# WeightGauge.net
KiCad netlist of a schematic drawn in EAGLE
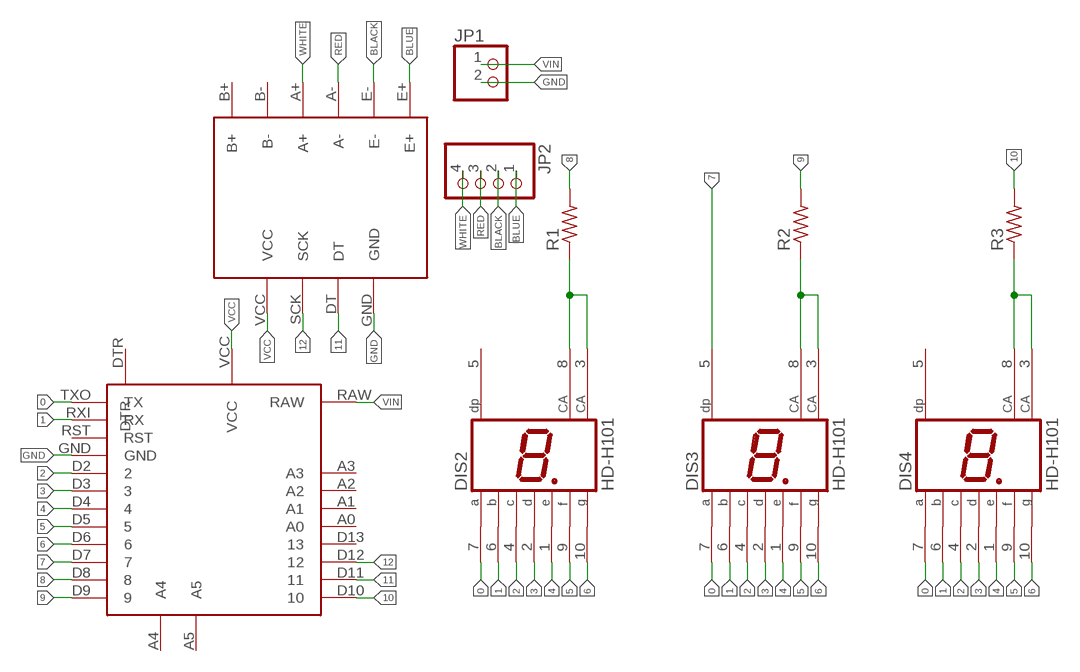
[diagram p0: schematic, sheet 1]

(export (version "E")
  (design (tool "Eeschema 10.0.6"))
  (components
    (comp (ref "DIS2")
      (value "HD-H101")
      (footprint "eagle-import:HDSP-M")
      (libsource (lib "eagle-import") (part "HD-H101"))
    )
    (comp (ref "DIS3")
      (value "HD-H101")
      (footprint "eagle-import:HDSP-M")
      (libsource (lib "eagle-import") (part "HD-H101"))
    )
    (comp (ref "DIS4")
      (value "HD-H101")
      (footprint "eagle-import:HDSP-M")
      (libsource (lib "eagle-import") (part "HD-H101"))
    )
    (comp (ref "JP1")
      (value "PINHD-1X2/90")
      (footprint "eagle-import:1X02_90")
      (libsource (lib "eagle-import") (part "PINHD-1X2/90"))
    )
    (comp (ref "JP2")
      (value "PINHD-1X4/90")
      (footprint "eagle-import:1X04_90")
      (libsource (lib "eagle-import") (part "PINHD-1X4/90"))
    )
    (comp (ref "R1")
      (value "R-US_R1206")
      (footprint "eagle-import:R1206")
      (libsource (lib "eagle-import") (part "R-US_R1206"))
    )
    (comp (ref "R2")
      (value "R-US_R1206")
      (footprint "eagle-import:R1206")
      (libsource (lib "eagle-import") (part "R-US_R1206"))
    )
    (comp (ref "R3")
      (value "R-US_R1206")
      (footprint "eagle-import:R1206")
      (libsource (lib "eagle-import") (part "R-US_R1206"))
    )
    (comp (ref "U$1")
      (value "ARDUINO_PRO_MINI")
      (footprint "eagle-import:ARDUINO_PRO_MINI")
      (libsource (lib "eagle-import") (part "ARDUINO_PRO_MINI"))
    )
    (comp (ref "U$2")
      (value "HX711")
      (footprint "eagle-import:HX711")
      (libsource (lib "eagle-import") (part "HX711"))
    )
  )
  (nets
    (net (code "1") (name "0") (class "Default")
      (node (ref "DIS2") (pin "7") (pinfunction "A_7") (pintype "passive"))
      (node (ref "DIS3") (pin "7") (pinfunction "A_7") (pintype "passive"))
      (node (ref "DIS4") (pin "7") (pinfunction "A_7") (pintype "passive"))
      (node (ref "U$1") (pin "TXO") (pinfunction "TX_TXO") (pintype "bidirectional"))
    )
    (net (code "2") (name "1") (class "Default")
      (node (ref "DIS2") (pin "6") (pinfunction "B_6") (pintype "passive"))
      (node (ref "DIS3") (pin "6") (pinfunction "B_6") (pintype "passive"))
      (node (ref "DIS4") (pin "6") (pinfunction "B_6") (pintype "passive"))
      (node (ref "U$1") (pin "RXI") (pinfunction "RX_RXI") (pintype "bidirectional"))
    )
    (net (code "3") (name "2") (class "Default")
      (node (ref "DIS2") (pin "4") (pinfunction "C_4") (pintype "passive"))
      (node (ref "DIS3") (pin "4") (pinfunction "C_4") (pintype "passive"))
      (node (ref "DIS4") (pin "4") (pinfunction "C_4") (pintype "passive"))
      (node (ref "U$1") (pin "D2") (pinfunction "2_D2") (pintype "bidirectional"))
    )
    (net (code "4") (name "3") (class "Default")
      (node (ref "DIS2") (pin "2") (pinfunction "D_2") (pintype "passive"))
      (node (ref "DIS3") (pin "2") (pinfunction "D_2") (pintype "passive"))
      (node (ref "DIS4") (pin "2") (pinfunction "D_2") (pintype "passive"))
      (node (ref "U$1") (pin "D3") (pinfunction "3_D3") (pintype "bidirectional"))
    )
    (net (code "5") (name "4") (class "Default")
      (node (ref "DIS2") (pin "1") (pinfunction "E_1") (pintype "passive"))
      (node (ref "DIS3") (pin "1") (pinfunction "E_1") (pintype "passive"))
      (node (ref "DIS4") (pin "1") (pinfunction "E_1") (pintype "passive"))
      (node (ref "U$1") (pin "D4") (pinfunction "4_D4") (pintype "bidirectional"))
    )
    (net (code "6") (name "5") (class "Default")
      (node (ref "DIS2") (pin "9") (pinfunction "F_9") (pintype "passive"))
      (node (ref "DIS3") (pin "9") (pinfunction "F_9") (pintype "passive"))
      (node (ref "DIS4") (pin "9") (pinfunction "F_9") (pintype "passive"))
      (node (ref "U$1") (pin "D5") (pinfunction "5_D5") (pintype "bidirectional"))
    )
    (net (code "7") (name "6") (class "Default")
      (node (ref "DIS2") (pin "10") (pinfunction "G_10") (pintype "passive"))
      (node (ref "DIS3") (pin "10") (pinfunction "G_10") (pintype "passive"))
      (node (ref "DIS4") (pin "10") (pinfunction "G_10") (pintype "passive"))
      (node (ref "U$1") (pin "D6") (pinfunction "6_D6") (pintype "bidirectional"))
    )
    (net (code "8") (name "7") (class "Default")
      (node (ref "DIS3") (pin "5") (pinfunction "DP_5") (pintype "passive"))
      (node (ref "U$1") (pin "D7") (pinfunction "7_D7") (pintype "bidirectional"))
    )
    (net (code "9") (name "8") (class "Default")
      (node (ref "R1") (pin "2") (pinfunction "2_2") (pintype "passive"))
      (node (ref "U$1") (pin "D8") (pinfunction "8_D8") (pintype "bidirectional"))
    )
    (net (code "10") (name "9") (class "Default")
      (node (ref "R2") (pin "2") (pinfunction "2_2") (pintype "passive"))
      (node (ref "U$1") (pin "D9") (pinfunction "9_D9") (pintype "bidirectional"))
    )
    (net (code "11") (name "10") (class "Default")
      (node (ref "R3") (pin "2") (pinfunction "2_2") (pintype "passive"))
      (node (ref "U$1") (pin "D10") (pinfunction "10_D10") (pintype "bidirectional"))
    )
    (net (code "12") (name "11") (class "Default")
      (node (ref "U$1") (pin "D11") (pinfunction "11_D11") (pintype "bidirectional"))
      (node (ref "U$2") (pin "DT") (pinfunction "DT_DT") (pintype "bidirectional"))
    )
    (net (code "13") (name "12") (class "Default")
      (node (ref "U$1") (pin "D12") (pinfunction "12_D12") (pintype "bidirectional"))
      (node (ref "U$2") (pin "SCK") (pinfunction "SCK_SCK") (pintype "bidirectional"))
    )
    (net (code "14") (name "BLACK") (class "Default")
      (node (ref "JP2") (pin "2") (pinfunction "2_2") (pintype "passive"))
      (node (ref "U$2") (pin "E-") (pinfunction "E-_E-") (pintype "bidirectional"))
    )
    (net (code "15") (name "BLUE") (class "Default")
      (node (ref "JP2") (pin "1") (pinfunction "1_1") (pintype "passive"))
      (node (ref "U$2") (pin "E+") (pinfunction "E+_E+") (pintype "bidirectional"))
    )
    (net (code "16") (name "GND") (class "Default")
      (node (ref "JP1") (pin "2") (pinfunction "2_2") (pintype "passive"))
      (node (ref "U$1") (pin "GND") (pinfunction "GND_GND") (pintype "bidirectional"))
      (node (ref "U$2") (pin "GND") (pinfunction "GND_GND") (pintype "bidirectional"))
    )
    (net (code "17") (name "Net-(DIS2-CA-Pad3)") (class "Default")
      (node (ref "DIS2") (pin "3") (pinfunction "CA_3") (pintype "passive"))
      (node (ref "DIS2") (pin "8") (pinfunction "CA_8") (pintype "passive"))
      (node (ref "R1") (pin "1") (pinfunction "1_1") (pintype "passive"))
    )
    (net (code "18") (name "Net-(DIS3-CA-Pad3)") (class "Default")
      (node (ref "DIS3") (pin "3") (pinfunction "CA_3") (pintype "passive"))
      (node (ref "DIS3") (pin "8") (pinfunction "CA_8") (pintype "passive"))
      (node (ref "R2") (pin "1") (pinfunction "1_1") (pintype "passive"))
    )
    (net (code "19") (name "Net-(DIS4-CA-Pad3)") (class "Default")
      (node (ref "DIS4") (pin "3") (pinfunction "CA_3") (pintype "passive"))
      (node (ref "DIS4") (pin "8") (pinfunction "CA_8") (pintype "passive"))
      (node (ref "R3") (pin "1") (pinfunction "1_1") (pintype "passive"))
    )
    (net (code "20") (name "RED") (class "Default")
      (node (ref "JP2") (pin "3") (pinfunction "3_3") (pintype "passive"))
      (node (ref "U$2") (pin "A-") (pinfunction "A-_A-") (pintype "bidirectional"))
    )
    (net (code "21") (name "VCC") (class "Default")
      (node (ref "U$1") (pin "VCC") (pinfunction "VCC_VCC") (pintype "bidirectional"))
      (node (ref "U$2") (pin "VCC") (pinfunction "VCC_VCC") (pintype "bidirectional"))
    )
    (net (code "22") (name "VIN") (class "Default")
      (node (ref "JP1") (pin "1") (pinfunction "1_1") (pintype "passive"))
      (node (ref "U$1") (pin "RAW") (pinfunction "RAW_RAW") (pintype "bidirectional"))
    )
    (net (code "23") (name "WHITE") (class "Default")
      (node (ref "JP2") (pin "4") (pinfunction "4_4") (pintype "passive"))
      (node (ref "U$2") (pin "A+") (pinfunction "A+_A+") (pintype "bidirectional"))
    )
    (net (code "24") (name "unconnected-(DIS2-DP-Pad5)") (class "Default")
      (node (ref "DIS2") (pin "5") (pinfunction "DP_5") (pintype "passive"))
    )
    (net (code "25") (name "unconnected-(DIS4-DP-Pad5)") (class "Default")
      (node (ref "DIS4") (pin "5") (pinfunction "DP_5") (pintype "passive"))
    )
    (net (code "26") (name "unconnected-(U$1-13-PadD13)") (class "Default")
      (node (ref "U$1") (pin "D13") (pinfunction "13_D13") (pintype "bidirectional"))
    )
    (net (code "27") (name "unconnected-(U$1-PadA0)") (class "Default")
      (node (ref "U$1") (pin "A0") (pinfunction "A0_A0") (pintype "bidirectional"))
    )
    (net (code "28") (name "unconnected-(U$1-PadA1)") (class "Default")
      (node (ref "U$1") (pin "A1") (pinfunction "A1_A1") (pintype "bidirectional"))
    )
    (net (code "29") (name "unconnected-(U$1-PadA2)") (class "Default")
      (node (ref "U$1") (pin "A2") (pinfunction "A2_A2") (pintype "bidirectional"))
    )
    (net (code "30") (name "unconnected-(U$1-PadA3)") (class "Default")
      (node (ref "U$1") (pin "A3") (pinfunction "A3_A3") (pintype "bidirectional"))
    )
    (net (code "31") (name "unconnected-(U$1-PadA4)") (class "Default")
      (node (ref "U$1") (pin "A4") (pinfunction "A4_A4") (pintype "bidirectional"))
    )
    (net (code "32") (name "unconnected-(U$1-PadA5)") (class "Default")
      (node (ref "U$1") (pin "A5") (pinfunction "A5_A5") (pintype "bidirectional"))
    )
    (net (code "33") (name "unconnected-(U$1-PadDTR)") (class "Default")
      (node (ref "U$1") (pin "DTR") (pinfunction "DTR_DTR") (pintype "bidirectional"))
    )
    (net (code "34") (name "unconnected-(U$1-PadRST)") (class "Default")
      (node (ref "U$1") (pin "RST") (pinfunction "RST_RST") (pintype "bidirectional"))
    )
    (net (code "35") (name "unconnected-(U$2-PadB+)") (class "Default")
      (node (ref "U$2") (pin "B+") (pinfunction "B+_B+") (pintype "bidirectional"))
    )
    (net (code "36") (name "unconnected-(U$2-PadB-)") (class "Default")
      (node (ref "U$2") (pin "B-") (pinfunction "B-_B-") (pintype "bidirectional"))
    )
  )
)
